# Pin_Connections.net
KiCad netlist of a schematic drawn in Altium Designer
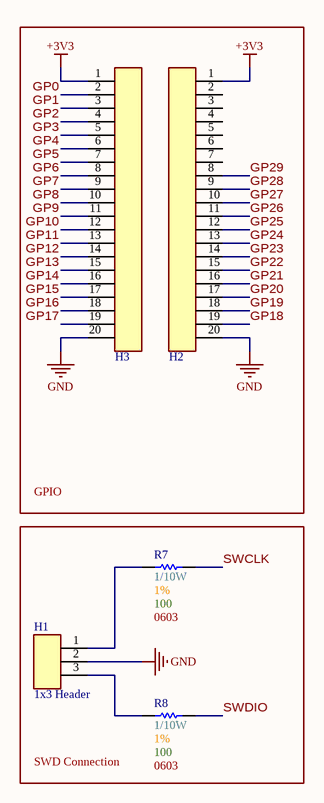
[diagram p0: Pin Connections.SchDoc]

(export (version "E")
  (design (tool "Eeschema 10.0.6"))
  (components
    (comp (ref "H1")
      (value "1x3 Header")
      (footprint "[Header] 1x3 Male")
      (description "2.54mm pitch")
      (libsource (lib "Connectors") (part "[Header] 1x3 Male"))
    )
    (comp (ref "H2")
      (value "1x20 Header")
      (footprint "[Header] 1x20 Male")
      (description "2.54mm pitch")
      (libsource (lib "Connectors") (part "[Header] 1x20 Male"))
    )
    (comp (ref "H3")
      (value "1x20 Header")
      (footprint "[Header] 1x20 Male")
      (description "2.54mm pitch")
      (libsource (lib "") (part "[Header] 1x20 Male_1"))
    )
    (comp (ref "R7")
      (value "[100] SMD 0603 1% 1/10W")
      (footprint "[Res] SMD 0603")
      (description "RC0603FR-07100RL")
      (fields
        (field (name "WATTAGE") "1/10W")
        (field (name "TOLERANCE") "1%")
        (field (name "RESISTANCE") "100")
        (field (name "SIZE PACKAGE") "0603")
      )
      (libsource (lib "Resistors") (part "[100] SMD 0603 1% 1/10W"))
    )
    (comp (ref "R8")
      (value "[100] SMD 0603 1% 1/10W")
      (footprint "[Res] SMD 0603")
      (description "RC0603FR-07100RL")
      (fields
        (field (name "WATTAGE") "1/10W")
        (field (name "TOLERANCE") "1%")
        (field (name "RESISTANCE") "100")
        (field (name "SIZE PACKAGE") "0603")
      )
      (libsource (lib "Resistors") (part "[100] SMD 0603 1% 1/10W"))
    )
  )
  (nets
    (net (code "1") (name "+3V3") (class "Default")
      (node (ref "H2") (pin "1") (pinfunction "1_1") (pintype "passive"))
      (node (ref "H3") (pin "1") (pinfunction "1_1") (pintype "passive"))
    )
    (net (code "2") (name "/GP0") (class "Default")
      (node (ref "H3") (pin "2") (pinfunction "2_2") (pintype "passive"))
    )
    (net (code "3") (name "/GP1") (class "Default")
      (node (ref "H3") (pin "3") (pinfunction "3_3") (pintype "passive"))
    )
    (net (code "4") (name "/GP2") (class "Default")
      (node (ref "H3") (pin "4") (pinfunction "4_4") (pintype "passive"))
    )
    (net (code "5") (name "/GP3") (class "Default")
      (node (ref "H3") (pin "5") (pinfunction "5_5") (pintype "passive"))
    )
    (net (code "6") (name "/GP4") (class "Default")
      (node (ref "H3") (pin "6") (pinfunction "6_6") (pintype "passive"))
    )
    (net (code "7") (name "/GP5") (class "Default")
      (node (ref "H3") (pin "7") (pinfunction "7_7") (pintype "passive"))
    )
    (net (code "8") (name "/GP6") (class "Default")
      (node (ref "H3") (pin "8") (pinfunction "8_8") (pintype "passive"))
    )
    (net (code "9") (name "/GP7") (class "Default")
      (node (ref "H3") (pin "9") (pinfunction "9_9") (pintype "passive"))
    )
    (net (code "10") (name "/GP8") (class "Default")
      (node (ref "H3") (pin "10") (pinfunction "10_10") (pintype "passive"))
    )
    (net (code "11") (name "/GP9") (class "Default")
      (node (ref "H3") (pin "11") (pinfunction "1_11") (pintype "passive"))
    )
    (net (code "12") (name "/GP10") (class "Default")
      (node (ref "H3") (pin "12") (pinfunction "2_12") (pintype "passive"))
    )
    (net (code "13") (name "/GP11") (class "Default")
      (node (ref "H3") (pin "13") (pinfunction "3_13") (pintype "passive"))
    )
    (net (code "14") (name "/GP12") (class "Default")
      (node (ref "H3") (pin "14") (pinfunction "4_14") (pintype "passive"))
    )
    (net (code "15") (name "/GP13") (class "Default")
      (node (ref "H3") (pin "15") (pinfunction "5_15") (pintype "passive"))
    )
    (net (code "16") (name "/GP14") (class "Default")
      (node (ref "H3") (pin "16") (pinfunction "6_16") (pintype "passive"))
    )
    (net (code "17") (name "/GP15") (class "Default")
      (node (ref "H3") (pin "17") (pinfunction "7_17") (pintype "passive"))
    )
    (net (code "18") (name "/GP16") (class "Default")
      (node (ref "H3") (pin "18") (pinfunction "8_18") (pintype "passive"))
    )
    (net (code "19") (name "/GP17") (class "Default")
      (node (ref "H3") (pin "19") (pinfunction "9_19") (pintype "passive"))
    )
    (net (code "20") (name "/GP18") (class "Default")
      (node (ref "H2") (pin "19") (pinfunction "9_19") (pintype "passive"))
    )
    (net (code "21") (name "/GP19") (class "Default")
      (node (ref "H2") (pin "18") (pinfunction "8_18") (pintype "passive"))
    )
    (net (code "22") (name "/GP20") (class "Default")
      (node (ref "H2") (pin "17") (pinfunction "7_17") (pintype "passive"))
    )
    (net (code "23") (name "/GP21") (class "Default")
      (node (ref "H2") (pin "16") (pinfunction "6_16") (pintype "passive"))
    )
    (net (code "24") (name "/GP22") (class "Default")
      (node (ref "H2") (pin "15") (pinfunction "5_15") (pintype "passive"))
    )
    (net (code "25") (name "/GP23") (class "Default")
      (node (ref "H2") (pin "14") (pinfunction "4_14") (pintype "passive"))
    )
    (net (code "26") (name "/GP24") (class "Default")
      (node (ref "H2") (pin "13") (pinfunction "3_13") (pintype "passive"))
    )
    (net (code "27") (name "/GP25") (class "Default")
      (node (ref "H2") (pin "12") (pinfunction "2_12") (pintype "passive"))
    )
    (net (code "28") (name "/GP26") (class "Default")
      (node (ref "H2") (pin "11") (pinfunction "1_11") (pintype "passive"))
    )
    (net (code "29") (name "/GP27") (class "Default")
      (node (ref "H2") (pin "10") (pinfunction "10_10") (pintype "passive"))
    )
    (net (code "30") (name "/GP28") (class "Default")
      (node (ref "H2") (pin "9") (pinfunction "9_9") (pintype "passive"))
    )
    (net (code "31") (name "/GP29") (class "Default")
      (node (ref "H2") (pin "8") (pinfunction "8_8") (pintype "passive"))
    )
    (net (code "32") (name "/SWCLK") (class "Default")
      (node (ref "R7") (pin "2") (pinfunction "2_2") (pintype "passive"))
    )
    (net (code "33") (name "/SWDIO") (class "Default")
      (node (ref "R8") (pin "2") (pinfunction "2_2") (pintype "passive"))
    )
    (net (code "34") (name "GND") (class "Default")
      (node (ref "H1") (pin "2") (pintype "passive"))
      (node (ref "H2") (pin "20") (pinfunction "10_20") (pintype "passive"))
      (node (ref "H3") (pin "20") (pinfunction "10_20") (pintype "passive"))
    )
    (net (code "35") (name "Net-(H1-Pad1)") (class "Default")
      (node (ref "H1") (pin "1") (pintype "passive"))
      (node (ref "R7") (pin "1") (pinfunction "1_1") (pintype "passive"))
    )
    (net (code "36") (name "Net-(H1-Pad3)") (class "Default")
      (node (ref "H1") (pin "3") (pintype "passive"))
      (node (ref "R8") (pin "1") (pinfunction "1_1") (pintype "passive"))
    )
    (net (code "37") (name "unconnected-(H2-Pad2)") (class "Default")
      (node (ref "H2") (pin "2") (pinfunction "2_2") (pintype "passive"))
    )
    (net (code "38") (name "unconnected-(H2-Pad3)") (class "Default")
      (node (ref "H2") (pin "3") (pinfunction "3_3") (pintype "passive"))
    )
    (net (code "39") (name "unconnected-(H2-Pad4)") (class "Default")
      (node (ref "H2") (pin "4") (pinfunction "4_4") (pintype "passive"))
    )
    (net (code "40") (name "unconnected-(H2-Pad5)") (class "Default")
      (node (ref "H2") (pin "5") (pinfunction "5_5") (pintype "passive"))
    )
    (net (code "41") (name "unconnected-(H2-Pad6)") (class "Default")
      (node (ref "H2") (pin "6") (pinfunction "6_6") (pintype "passive"))
    )
    (net (code "42") (name "unconnected-(H2-Pad7)") (class "Default")
      (node (ref "H2") (pin "7") (pinfunction "7_7") (pintype "passive"))
    )
  )
)
